# MCP2515.net
KiCad netlist of a schematic drawn in Altium Designer
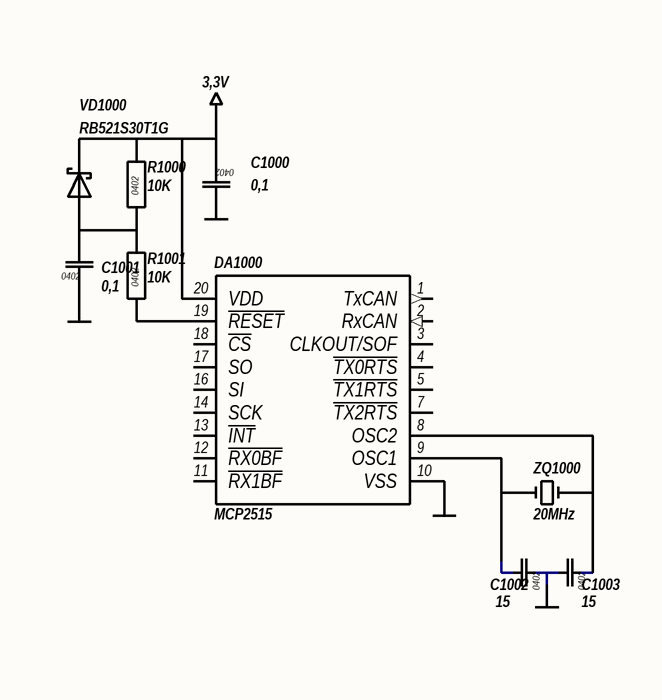
[diagram p0: MCP2515.SchDoc]

(export (version "E")
  (design (tool "Eeschema 10.0.6"))
  (components
    (comp (ref "C1000")
      (value "0,1")
      (footprint "CAP0402")
      (description "Конденсатор чип")
      (libsource (lib "EwgPassive") (part "CAP_0402"))
    )
    (comp (ref "C1001")
      (value "0,1")
      (footprint "CAP0402")
      (description "Конденсатор чип")
      (libsource (lib "EwgPassive") (part "CAP_0402"))
    )
    (comp (ref "C1002")
      (value "15")
      (footprint "CAP0402")
      (description "Конденсатор чип")
      (libsource (lib "EwgPassive") (part "CAP_0402"))
    )
    (comp (ref "C1003")
      (value "15")
      (footprint "CAP0402")
      (description "Конденсатор чип")
      (libsource (lib "EwgPassive") (part "CAP_0402"))
    )
    (comp (ref "DA1000")
      (value "MCP2515")
      (footprint "SSOP20-4.4")
      (description "Интерфейс CAN SPI")
      (libsource (lib "EwgMicrochips") (part "MCP2515"))
    )
    (comp (ref "R1000")
      (value "10K")
      (footprint "RES0402")
      (description "Резистор чип")
      (libsource (lib "EwgPassive") (part "RES_0402"))
    )
    (comp (ref "R1001")
      (value "10K")
      (footprint "RES0402")
      (description "Резистор чип")
      (libsource (lib "EwgPassive") (part "RES_0402"))
    )
    (comp (ref "VD1000")
      (value "RB521S30T1G")
      (footprint "SOD-523F")
      (description "Диод Шоттки")
      (libsource (lib "EwgActive") (part "RB521S30T1G"))
    )
    (comp (ref "ZQ1000")
      (value "20MHz")
      (footprint "KX-7")
      (description "Кварц")
      (libsource (lib "EwgPassive") (part "KX-7"))
    )
  )
  (nets
    (net (code "1") (name "3,3V") (class "Default")
      (node (ref "C1000") (pin "1") (pintype "passive"))
      (node (ref "DA1000") (pin "20") (pinfunction "VDD_20") (pintype "passive"))
      (node (ref "R1000") (pin "2") (pintype "passive"))
      (node (ref "VD1000") (pin "2") (pintype "passive"))
    )
    (net (code "2") (name "GND") (class "Default")
      (node (ref "C1000") (pin "2") (pintype "passive"))
      (node (ref "C1001") (pin "1") (pintype "passive"))
      (node (ref "C1002") (pin "1") (pintype "passive"))
      (node (ref "C1003") (pin "2") (pintype "passive"))
      (node (ref "DA1000") (pin "10") (pinfunction "VSS_10") (pintype "passive"))
    )
    (net (code "3") (name "Net-(C1001-Pad2)") (class "Default")
      (node (ref "C1001") (pin "2") (pintype "passive"))
      (node (ref "R1000") (pin "1") (pintype "passive"))
      (node (ref "R1001") (pin "2") (pintype "passive"))
      (node (ref "VD1000") (pin "1") (pintype "passive"))
    )
    (net (code "4") (name "Net-(DA1000-OSC1)") (class "Default")
      (node (ref "C1002") (pin "2") (pintype "passive"))
      (node (ref "DA1000") (pin "9") (pinfunction "OSC1_9") (pintype "passive"))
      (node (ref "ZQ1000") (pin "3") (pintype "passive"))
    )
    (net (code "5") (name "Net-(DA1000-OSC2)") (class "Default")
      (node (ref "C1003") (pin "1") (pintype "passive"))
      (node (ref "DA1000") (pin "8") (pinfunction "OSC2_8") (pintype "passive"))
      (node (ref "ZQ1000") (pin "1") (pintype "passive"))
    )
    (net (code "6") (name "Net-(DA1000-~{RESET})") (class "Default")
      (node (ref "DA1000") (pin "19") (pinfunction "~{RESET}_19") (pintype "passive"))
      (node (ref "R1001") (pin "1") (pintype "passive"))
    )
    (net (code "7") (name "unconnected-(DA1000-CLKOUT{slash}SOF-Pad3)") (class "Default")
      (node (ref "DA1000") (pin "3") (pinfunction "CLKOUT/SOF_3") (pintype "passive"))
    )
    (net (code "8") (name "unconnected-(DA1000-RxCAN-Pad2)") (class "Default")
      (node (ref "DA1000") (pin "2") (pinfunction "RxCAN_2") (pintype "input"))
    )
    (net (code "9") (name "unconnected-(DA1000-SCK-Pad14)") (class "Default")
      (node (ref "DA1000") (pin "14") (pinfunction "SCK_14") (pintype "passive"))
    )
    (net (code "10") (name "unconnected-(DA1000-SI-Pad16)") (class "Default")
      (node (ref "DA1000") (pin "16") (pinfunction "SI_16") (pintype "passive"))
    )
    (net (code "11") (name "unconnected-(DA1000-SO-Pad17)") (class "Default")
      (node (ref "DA1000") (pin "17") (pinfunction "SO_17") (pintype "passive"))
    )
    (net (code "12") (name "unconnected-(DA1000-TxCAN-Pad1)") (class "Default")
      (node (ref "DA1000") (pin "1") (pinfunction "TxCAN_1") (pintype "output"))
    )
    (net (code "13") (name "unconnected-(DA1000-~{CS}-Pad18)") (class "Default")
      (node (ref "DA1000") (pin "18") (pinfunction "~{CS}_18") (pintype "passive"))
    )
    (net (code "14") (name "unconnected-(DA1000-~{INT}-Pad13)") (class "Default")
      (node (ref "DA1000") (pin "13") (pinfunction "~{INT}_13") (pintype "passive"))
    )
    (net (code "15") (name "unconnected-(DA1000-~{RX0BF}-Pad12)") (class "Default")
      (node (ref "DA1000") (pin "12") (pinfunction "~{RX0BF}_12") (pintype "passive"))
    )
    (net (code "16") (name "unconnected-(DA1000-~{RX1BF}-Pad11)") (class "Default")
      (node (ref "DA1000") (pin "11") (pinfunction "~{RX1BF}_11") (pintype "passive"))
    )
    (net (code "17") (name "unconnected-(DA1000-~{TX0RTS}-Pad4)") (class "Default")
      (node (ref "DA1000") (pin "4") (pinfunction "~{TX0RTS}_4") (pintype "passive"))
    )
    (net (code "18") (name "unconnected-(DA1000-~{TX1RTS}-Pad5)") (class "Default")
      (node (ref "DA1000") (pin "5") (pinfunction "~{TX1RTS}_5") (pintype "passive"))
    )
    (net (code "19") (name "unconnected-(DA1000-~{TX2RTS}-Pad7)") (class "Default")
      (node (ref "DA1000") (pin "7") (pinfunction "~{TX2RTS}_7") (pintype "passive"))
    )
    (net (code "20") (name "unconnected-(ZQ1000-Pad2)") (class "Default")
      (node (ref "ZQ1000") (pin "2") (pintype "passive"))
    )
    (net (code "21") (name "unconnected-(ZQ1000-Pad4)") (class "Default")
      (node (ref "ZQ1000") (pin "4") (pintype "passive"))
    )
  )
)
